# mg.net
KiCad netlist of a schematic drawn in EAGLE
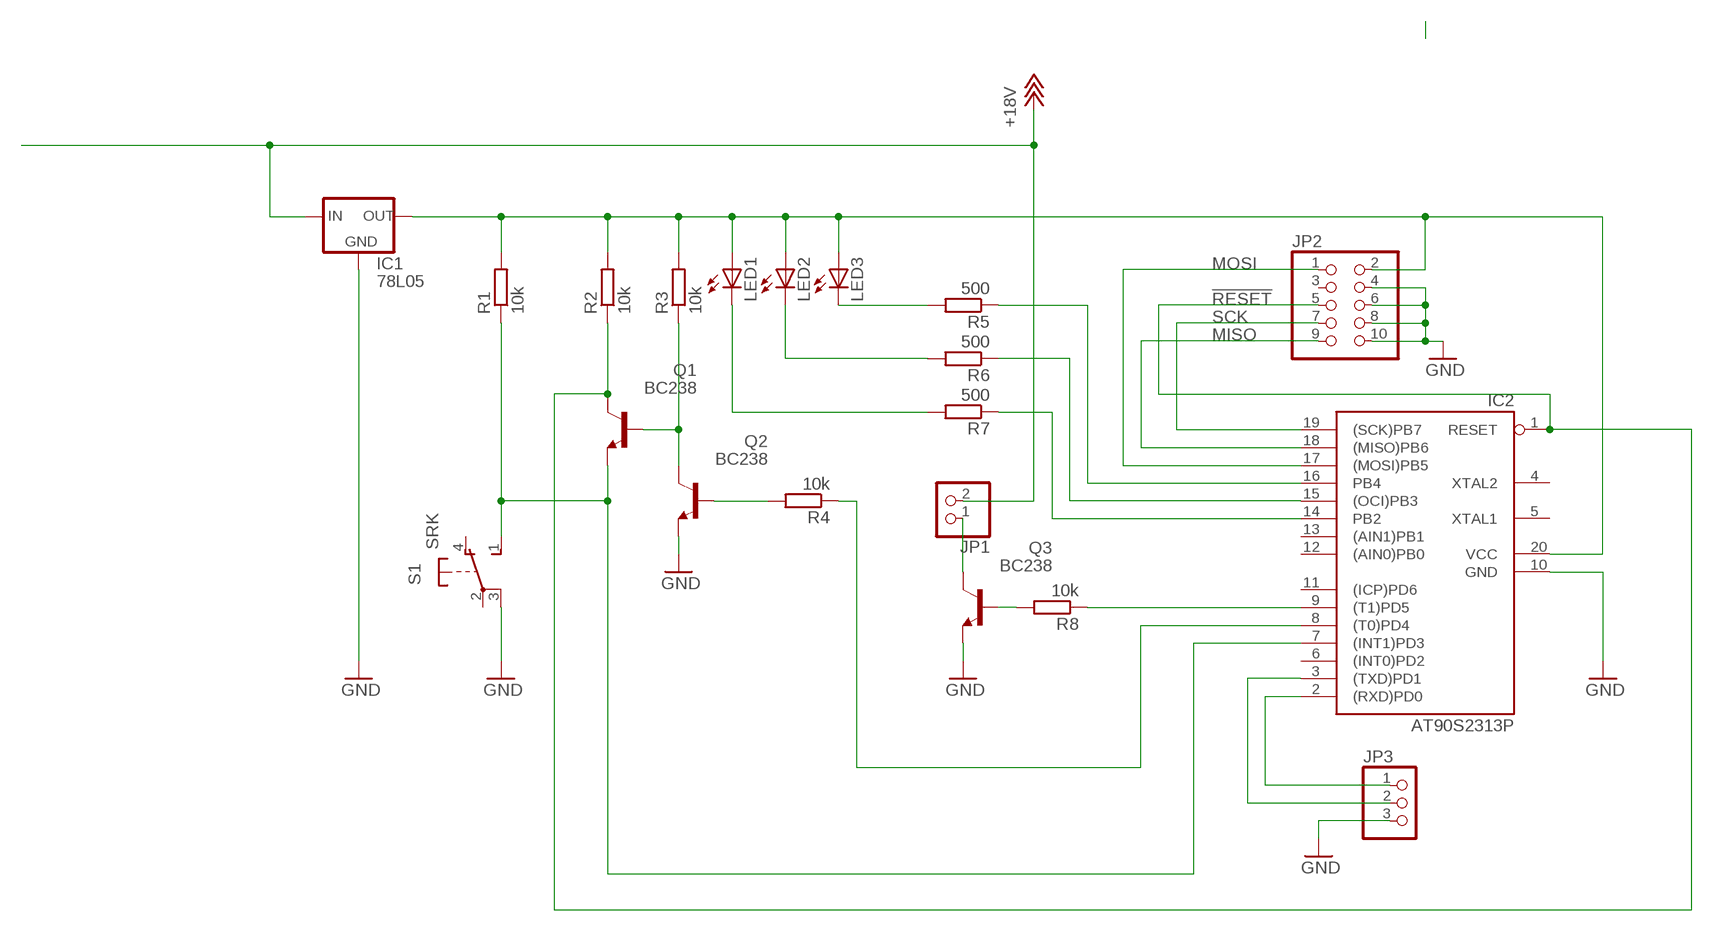
[diagram p0: schematic, sheet 1]

(export (version "E")
  (design (tool "Eeschema 10.0.6"))
  (components
    (comp (ref "IC1")
      (value "78L05")
      (footprint "eagle-import:78LXX")
      (libsource (lib "eagle-import") (part "78LXX"))
    )
    (comp (ref "IC2")
      (value "AT90S2313P")
      (footprint "eagle-import:DIL20")
      (libsource (lib "eagle-import") (part "AT90S2313P"))
    )
    (comp (ref "JP1")
      (value "PINHD-1X2")
      (footprint "eagle-import:1X02")
      (libsource (lib "eagle-import") (part "PINHD-1X2"))
    )
    (comp (ref "JP2")
      (value "PINHD-2X5")
      (footprint "eagle-import:2X05")
      (libsource (lib "eagle-import") (part "PINHD-2X5"))
    )
    (comp (ref "JP3")
      (value "PINHD-1X3")
      (footprint "eagle-import:1X03")
      (libsource (lib "eagle-import") (part "PINHD-1X3"))
    )
    (comp (ref "LED1")
      (value "LED5MM")
      (footprint "eagle-import:LED5MM")
      (libsource (lib "eagle-import") (part "LED5MM"))
    )
    (comp (ref "LED2")
      (value "LED5MM")
      (footprint "eagle-import:LED5MM")
      (libsource (lib "eagle-import") (part "LED5MM"))
    )
    (comp (ref "LED3")
      (value "LED5MM")
      (footprint "eagle-import:LED5MM")
      (libsource (lib "eagle-import") (part "LED5MM"))
    )
    (comp (ref "Q1")
      (value "BC238")
      (footprint "eagle-import:TO92")
      (libsource (lib "eagle-import") (part "BC238"))
    )
    (comp (ref "Q2")
      (value "BC238")
      (footprint "eagle-import:TO92")
      (libsource (lib "eagle-import") (part "BC238"))
    )
    (comp (ref "Q3")
      (value "BC238")
      (footprint "eagle-import:TO92")
      (libsource (lib "eagle-import") (part "BC238"))
    )
    (comp (ref "R1")
      (value "10k")
      (footprint "eagle-import:0309_12")
      (libsource (lib "eagle-import") (part "R-EU_0309/12"))
    )
    (comp (ref "R2")
      (value "10k")
      (footprint "eagle-import:0309_12")
      (libsource (lib "eagle-import") (part "R-EU_0309/12"))
    )
    (comp (ref "R3")
      (value "10k")
      (footprint "eagle-import:0309_12")
      (libsource (lib "eagle-import") (part "R-EU_0309/12"))
    )
    (comp (ref "R4")
      (value "10k")
      (footprint "eagle-import:0309_12")
      (libsource (lib "eagle-import") (part "R-EU_0309/12"))
    )
    (comp (ref "R5")
      (value "500")
      (footprint "eagle-import:0309_12")
      (libsource (lib "eagle-import") (part "R-EU_0309/12"))
    )
    (comp (ref "R6")
      (value "500")
      (footprint "eagle-import:0309_12")
      (libsource (lib "eagle-import") (part "R-EU_0309/12"))
    )
    (comp (ref "R7")
      (value "500")
      (footprint "eagle-import:0309_12")
      (libsource (lib "eagle-import") (part "R-EU_0309/12"))
    )
    (comp (ref "R8")
      (value "10k")
      (footprint "eagle-import:0309_12")
      (libsource (lib "eagle-import") (part "R-EU_0309/12"))
    )
    (comp (ref "S1")
      (value "SRK")
      (footprint "eagle-import:SRK")
      (libsource (lib "eagle-import") (part "SRK"))
    )
  )
  (nets
    (net (code "1") (name "+18V") (class "Default")
      (node (ref "IC1") (pin "IN") (pinfunction "IN_IN") (pintype "input"))
      (node (ref "JP1") (pin "2") (pinfunction "2_2") (pintype "passive"))
    )
    (net (code "2") (name "/MISO") (class "Default")
      (node (ref "IC2") (pin "18") (pinfunction "(MISO)PB6_18") (pintype "bidirectional"))
      (node (ref "JP2") (pin "9") (pinfunction "9_9") (pintype "passive"))
    )
    (net (code "3") (name "/MOSI") (class "Default")
      (node (ref "IC2") (pin "17") (pinfunction "(MOSI)PB5_17") (pintype "bidirectional"))
      (node (ref "JP2") (pin "1") (pinfunction "1_1") (pintype "passive"))
    )
    (net (code "4") (name "/SCK") (class "Default")
      (node (ref "IC2") (pin "19") (pinfunction "(SCK)PB7_19") (pintype "bidirectional"))
      (node (ref "JP2") (pin "7") (pinfunction "7_7") (pintype "passive"))
    )
    (net (code "5") (name "/~{RESET}") (class "Default")
      (node (ref "IC2") (pin "1") (pinfunction "RESET_1") (pintype "bidirectional"))
      (node (ref "JP2") (pin "5") (pinfunction "5_5") (pintype "passive"))
      (node (ref "Q1") (pin "3") (pinfunction "C_3") (pintype "passive"))
      (node (ref "R2") (pin "1") (pinfunction "1_1") (pintype "passive"))
    )
    (net (code "6") (name "GND") (class "Default")
      (node (ref "IC1") (pin "GND") (pinfunction "GND_GND") (pintype "input"))
      (node (ref "IC2") (pin "10") (pinfunction "GND_10") (pintype "power_in"))
      (node (ref "JP2") (pin "10") (pinfunction "10_10") (pintype "passive"))
      (node (ref "JP2") (pin "4") (pinfunction "4_4") (pintype "passive"))
      (node (ref "JP2") (pin "6") (pinfunction "6_6") (pintype "passive"))
      (node (ref "JP2") (pin "8") (pinfunction "8_8") (pintype "passive"))
      (node (ref "JP3") (pin "3") (pinfunction "3_3") (pintype "passive"))
      (node (ref "Q2") (pin "1") (pinfunction "E_1") (pintype "passive"))
      (node (ref "Q3") (pin "1") (pinfunction "E_1") (pintype "passive"))
      (node (ref "S1") (pin "3") (pinfunction "P_3") (pintype "passive"))
    )
    (net (code "7") (name "Net-(IC2-(INT1)PD3)") (class "Default")
      (node (ref "IC2") (pin "7") (pinfunction "(INT1)PD3_7") (pintype "bidirectional"))
      (node (ref "Q1") (pin "1") (pinfunction "E_1") (pintype "passive"))
      (node (ref "R1") (pin "1") (pinfunction "1_1") (pintype "passive"))
      (node (ref "S1") (pin "1") (pinfunction "S_1") (pintype "passive"))
    )
    (net (code "8") (name "Net-(IC2-(OCI)PB3)") (class "Default")
      (node (ref "IC2") (pin "15") (pinfunction "(OCI)PB3_15") (pintype "bidirectional"))
      (node (ref "R6") (pin "1") (pinfunction "1_1") (pintype "passive"))
    )
    (net (code "9") (name "Net-(IC2-(RXD)PD0)") (class "Default")
      (node (ref "IC2") (pin "2") (pinfunction "(RXD)PD0_2") (pintype "bidirectional"))
      (node (ref "JP3") (pin "1") (pinfunction "1_1") (pintype "passive"))
    )
    (net (code "10") (name "Net-(IC2-(T0)PD4)") (class "Default")
      (node (ref "IC2") (pin "8") (pinfunction "(T0)PD4_8") (pintype "bidirectional"))
      (node (ref "R4") (pin "1") (pinfunction "1_1") (pintype "passive"))
    )
    (net (code "11") (name "Net-(IC2-(T1)PD5)") (class "Default")
      (node (ref "IC2") (pin "9") (pinfunction "(T1)PD5_9") (pintype "bidirectional"))
      (node (ref "R8") (pin "1") (pinfunction "1_1") (pintype "passive"))
    )
    (net (code "12") (name "Net-(IC2-(TXD)PD1)") (class "Default")
      (node (ref "IC2") (pin "3") (pinfunction "(TXD)PD1_3") (pintype "bidirectional"))
      (node (ref "JP3") (pin "2") (pinfunction "2_2") (pintype "passive"))
    )
    (net (code "13") (name "Net-(IC2-PB2)") (class "Default")
      (node (ref "IC2") (pin "14") (pinfunction "PB2_14") (pintype "bidirectional"))
      (node (ref "R7") (pin "1") (pinfunction "1_1") (pintype "passive"))
    )
    (net (code "14") (name "Net-(IC2-PB4)") (class "Default")
      (node (ref "IC2") (pin "16") (pinfunction "PB4_16") (pintype "bidirectional"))
      (node (ref "R5") (pin "1") (pinfunction "1_1") (pintype "passive"))
    )
    (net (code "15") (name "Net-(IC2-VCC)") (class "Default")
      (node (ref "IC1") (pin "OUT") (pinfunction "OUT_OUT") (pintype "passive"))
      (node (ref "IC2") (pin "20") (pinfunction "VCC_20") (pintype "power_in"))
      (node (ref "JP2") (pin "2") (pinfunction "2_2") (pintype "passive"))
      (node (ref "LED1") (pin "A") (pinfunction "A_A") (pintype "passive"))
      (node (ref "LED2") (pin "A") (pinfunction "A_A") (pintype "passive"))
      (node (ref "LED3") (pin "A") (pinfunction "A_A") (pintype "passive"))
      (node (ref "R1") (pin "2") (pinfunction "2_2") (pintype "passive"))
      (node (ref "R2") (pin "2") (pinfunction "2_2") (pintype "passive"))
      (node (ref "R3") (pin "2") (pinfunction "2_2") (pintype "passive"))
    )
    (net (code "16") (name "Net-(LED1-C)") (class "Default")
      (node (ref "LED1") (pin "K") (pinfunction "C_K") (pintype "passive"))
      (node (ref "R7") (pin "2") (pinfunction "2_2") (pintype "passive"))
    )
    (net (code "17") (name "Net-(LED2-C)") (class "Default")
      (node (ref "LED2") (pin "K") (pinfunction "C_K") (pintype "passive"))
      (node (ref "R6") (pin "2") (pinfunction "2_2") (pintype "passive"))
    )
    (net (code "18") (name "Net-(LED3-C)") (class "Default")
      (node (ref "LED3") (pin "K") (pinfunction "C_K") (pintype "passive"))
      (node (ref "R5") (pin "2") (pinfunction "2_2") (pintype "passive"))
    )
    (net (code "19") (name "Net-(Q1-B)") (class "Default")
      (node (ref "Q1") (pin "2") (pinfunction "B_2") (pintype "passive"))
      (node (ref "Q2") (pin "3") (pinfunction "C_3") (pintype "passive"))
      (node (ref "R3") (pin "1") (pinfunction "1_1") (pintype "passive"))
    )
    (net (code "20") (name "Net-(Q2-B)") (class "Default")
      (node (ref "Q2") (pin "2") (pinfunction "B_2") (pintype "passive"))
      (node (ref "R4") (pin "2") (pinfunction "2_2") (pintype "passive"))
    )
    (net (code "21") (name "Net-(Q3-B)") (class "Default")
      (node (ref "Q3") (pin "2") (pinfunction "B_2") (pintype "passive"))
      (node (ref "R8") (pin "2") (pinfunction "2_2") (pintype "passive"))
    )
    (net (code "22") (name "Net-(Q3-C)") (class "Default")
      (node (ref "JP1") (pin "1") (pinfunction "1_1") (pintype "passive"))
      (node (ref "Q3") (pin "3") (pinfunction "C_3") (pintype "passive"))
    )
    (net (code "23") (name "unconnected-(IC2-(AIN0)PB0-Pad12)") (class "Default")
      (node (ref "IC2") (pin "12") (pinfunction "(AIN0)PB0_12") (pintype "bidirectional"))
    )
    (net (code "24") (name "unconnected-(IC2-(AIN1)PB1-Pad13)") (class "Default")
      (node (ref "IC2") (pin "13") (pinfunction "(AIN1)PB1_13") (pintype "bidirectional"))
    )
    (net (code "25") (name "unconnected-(IC2-(ICP)PD6-Pad11)") (class "Default")
      (node (ref "IC2") (pin "11") (pinfunction "(ICP)PD6_11") (pintype "bidirectional"))
    )
    (net (code "26") (name "unconnected-(IC2-(INT0)PD2-Pad6)") (class "Default")
      (node (ref "IC2") (pin "6") (pinfunction "(INT0)PD2_6") (pintype "bidirectional"))
    )
    (net (code "27") (name "unconnected-(IC2-XTAL1-Pad5)") (class "Default")
      (node (ref "IC2") (pin "5") (pinfunction "XTAL1_5") (pintype "bidirectional"))
    )
    (net (code "28") (name "unconnected-(IC2-XTAL2-Pad4)") (class "Default")
      (node (ref "IC2") (pin "4") (pinfunction "XTAL2_4") (pintype "bidirectional"))
    )
    (net (code "29") (name "unconnected-(JP2-Pad3)") (class "Default")
      (node (ref "JP2") (pin "3") (pinfunction "3_3") (pintype "passive"))
    )
    (net (code "30") (name "unconnected-(S1-O-Pad4)") (class "Default")
      (node (ref "S1") (pin "4") (pinfunction "O_4") (pintype "passive"))
    )
    (net (code "31") (name "unconnected-(S1-P-Pad2)") (class "Default")
      (node (ref "S1") (pin "2") (pinfunction "P_2") (pintype "passive"))
    )
  )
)
